# Communications.net
KiCad netlist of a schematic drawn in Altium Designer
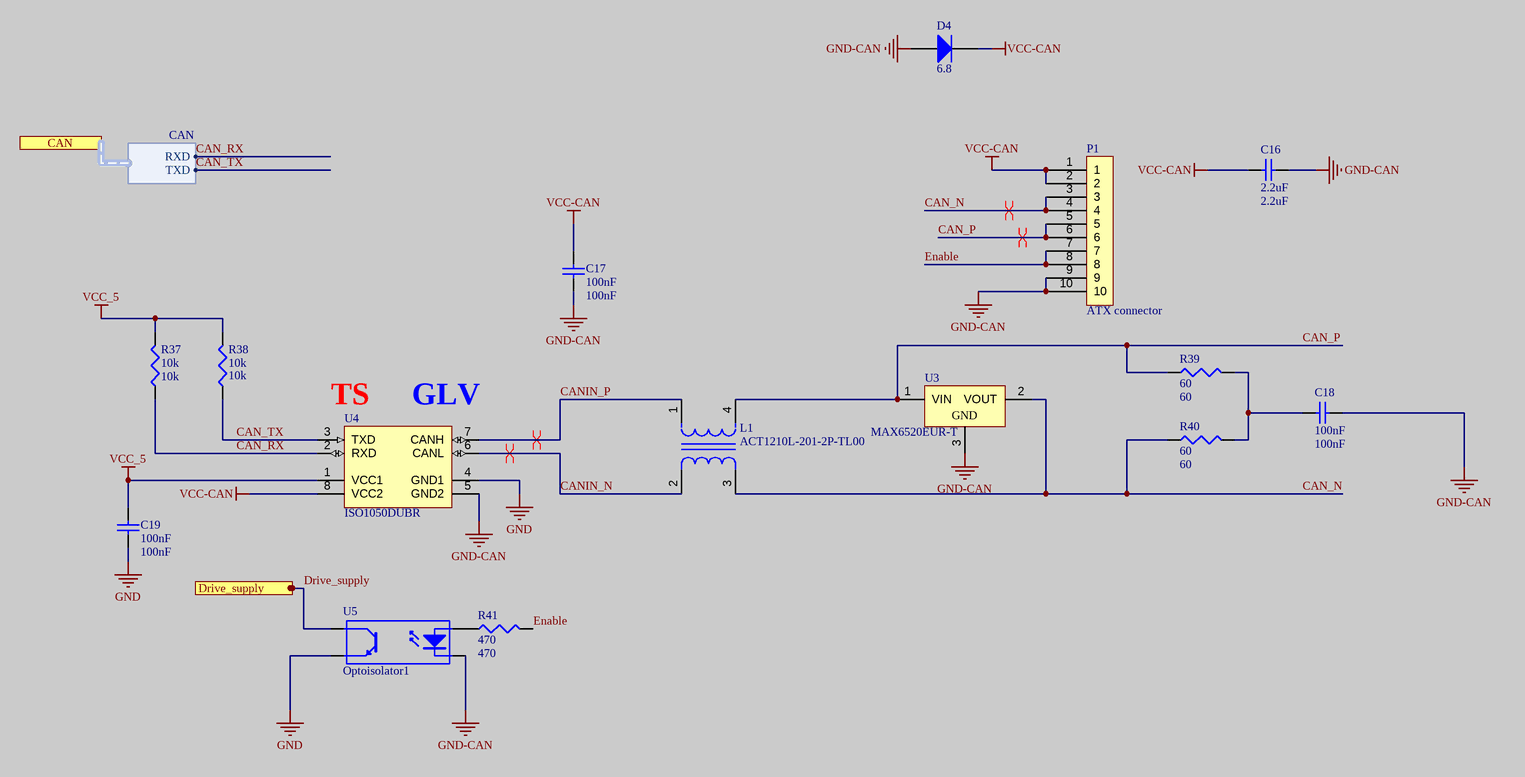
[diagram p0: Communications.SchDoc]

(export (version "E")
  (design (tool "Eeschema 10.0.6"))
  (components
    (comp (ref "C16")
      (value "2.2uF")
      (footprint "C0805")
      (description "Capacitor")
      (fields (field (name "ALTIUM_VALUE") "2.2uF") (field (name "PUBLISHER") "Altium Limited"))
      (libsource (lib "MyLibrary") (part "Capacitor"))
    )
    (comp (ref "C17")
      (value "100nF")
      (footprint "C0805")
      (description "Capacitor")
      (fields (field (name "ALTIUM_VALUE") "100nF") (field (name "PUBLISHER") "Altium Limited"))
      (libsource (lib "MyLibrary") (part "Capacitor"))
    )
    (comp (ref "C18")
      (value "100nF")
      (footprint "C0805")
      (description "Capacitor")
      (fields (field (name "ALTIUM_VALUE") "100nF") (field (name "PUBLISHER") "Altium Limited"))
      (libsource (lib "MyLibrary") (part "Capacitor"))
    )
    (comp (ref "C19")
      (value "100nF")
      (footprint "C0805")
      (description "Capacitor")
      (fields (field (name "ALTIUM_VALUE") "100nF") (field (name "PUBLISHER") "Altium Limited"))
      (libsource (lib "MyLibrary") (part "Capacitor"))
    )
    (comp (ref "D4")
      (value "6.8")
      (footprint "DIOD-SOD123-2_V")
      (description "Fast Switching Diode, 100 V, 0.15 A, -65 to 150 degC, 2-Pin?SOD123, RoHS, Tape and Reel")
      (fields (field (name "MANUFACTURER") "DiodesIncorporated"))
      (libsource (lib "1N4148W") (part "CMP-2000-04932-2"))
    )
    (comp (ref "L1")
      (value "ACT1210L-201-2P-TL00")
      (footprint "FP-ACT1210L-MFG")
      (description "CMC 200UH 70MA 2LN SMD")
      (fields
        (field (name "MANUFACTURER") "TDK")
        (field (name "OCTOPART") "https://octopart.com/act1210l-201-2p-tl00-tdk-81014617")
      )
      (libsource (lib "ACT1210L-201-2P-TL00") (part "CMP-08256-000003-1"))
    )
    (comp (ref "P1")
      (value "ATX connector")
      (footprint "ATX 10pin")
      (libsource (lib "MyLibrary") (part "ATX connector"))
    )
    (comp (ref "R37")
      (value "10k")
      (footprint "R0805")
      (description "Resistor")
      (fields (field (name "ALTIUM_VALUE") "10k") (field (name "PUBLISHER") "Altium Limited"))
      (libsource (lib "MyLibrary") (part "Resistor"))
    )
    (comp (ref "R38")
      (value "10k")
      (footprint "R0805")
      (description "Resistor")
      (fields (field (name "ALTIUM_VALUE") "10k") (field (name "PUBLISHER") "Altium Limited"))
      (libsource (lib "MyLibrary") (part "Resistor"))
    )
    (comp (ref "R39")
      (value "60")
      (footprint "R0805")
      (description "Resistor")
      (fields (field (name "ALTIUM_VALUE") "60") (field (name "PUBLISHER") "Altium Limited"))
      (libsource (lib "MyLibrary") (part "Resistor"))
    )
    (comp (ref "R40")
      (value "60")
      (footprint "R0805")
      (description "Resistor")
      (fields (field (name "ALTIUM_VALUE") "60") (field (name "PUBLISHER") "Altium Limited"))
      (libsource (lib "MyLibrary") (part "Resistor"))
    )
    (comp (ref "R41")
      (value "470")
      (footprint "R0805")
      (description "Resistor")
      (fields (field (name "ALTIUM_VALUE") "470") (field (name "PUBLISHER") "Altium Limited"))
      (libsource (lib "MyLibrary") (part "Resistor"))
    )
    (comp (ref "U3")
      (value "MAX6520EUR-T")
      (footprint "SOT23-3_N")
      (description "3-Terminal, 1.2V Voltage Reference")
      (fields (field (name "PUBLISHER") "Altium Limited"))
      (libsource (lib "Maxim Power Mgt Voltage Reference") (part "MAX6520EUR-T"))
    )
    (comp (ref "U4")
      (value "ISO1050DUBR")
      (footprint "DUB0008A_M")
      (description "Isolated CAN Transceiver, -55 to 105 degC, 8-pin SOP (DUB), Green (RoHS & no Sb/Br)")
      (fields (field (name "MANUFACTURER") "Texas Instruments"))
      (libsource (lib "Components - 05.09.22 - 15.55") (part "CMP-0315-00093-2"))
    )
    (comp (ref "U5")
      (value "Optoisolator1")
      (footprint "DIP-4")
      (description "4-Pin Phototransistor Optocoupler")
      (fields (field (name "PUBLISHER") "Altium Limited"))
      (libsource (lib "Miscellaneous Devices") (part "Optoisolator1"))
    )
  )
  (nets
    (net (code "2") (name "/CANIN_N") (class "Default")
      (node (ref "L1") (pin "2") (pinfunction "2_2") (pintype "passive"))
      (node (ref "U4") (pin "6") (pinfunction "CANL_6") (pintype "bidirectional"))
    )
    (net (code "3") (name "/CANIN_P") (class "Default")
      (node (ref "L1") (pin "1") (pinfunction "1_1") (pintype "passive"))
      (node (ref "U4") (pin "7") (pinfunction "CANH_7") (pintype "bidirectional"))
    )
    (net (code "4") (name "/CAN_N") (class "Default")
      (node (ref "L1") (pin "3") (pinfunction "3_3") (pintype "passive"))
      (node (ref "P1") (pin "3") (pinfunction "3_3") (pintype "passive"))
      (node (ref "P1") (pin "4") (pinfunction "4_4") (pintype "passive"))
      (node (ref "R40") (pin "1") (pinfunction "1_1") (pintype "passive"))
      (node (ref "U3") (pin "2") (pinfunction "VOUT_2") (pintype "passive"))
    )
    (net (code "5") (name "/CAN_P") (class "Default")
      (node (ref "L1") (pin "4") (pinfunction "4_4") (pintype "passive"))
      (node (ref "P1") (pin "5") (pinfunction "5_5") (pintype "passive"))
      (node (ref "P1") (pin "6") (pinfunction "6_6") (pintype "passive"))
      (node (ref "R39") (pin "1") (pinfunction "1_1") (pintype "passive"))
      (node (ref "U3") (pin "1") (pinfunction "VIN_1") (pintype "passive"))
    )
    (net (code "6") (name "/CAN_RX") (class "Default")
      (node (ref "R37") (pin "1") (pinfunction "1_1") (pintype "passive"))
      (node (ref "U4") (pin "2") (pinfunction "RXD_2") (pintype "bidirectional"))
    )
    (net (code "7") (name "/CAN_TX") (class "Default")
      (node (ref "R38") (pin "1") (pinfunction "1_1") (pintype "passive"))
      (node (ref "U4") (pin "3") (pinfunction "TXD_3") (pintype "input"))
    )
    (net (code "8") (name "/Drive_supply") (class "Default")
      (node (ref "U5") (pin "4") (pinfunction "C_4") (pintype "passive"))
    )
    (net (code "9") (name "/Enable") (class "Default")
      (node (ref "P1") (pin "7") (pinfunction "7_7") (pintype "passive"))
      (node (ref "P1") (pin "8") (pinfunction "8_8") (pintype "passive"))
      (node (ref "R41") (pin "2") (pinfunction "2_2") (pintype "passive"))
    )
    (net (code "11") (name "GND") (class "Default")
      (node (ref "C19") (pin "2") (pinfunction "2_2") (pintype "passive"))
      (node (ref "U4") (pin "4") (pinfunction "GND1_4") (pintype "power_in"))
      (node (ref "U5") (pin "3") (pinfunction "E_3") (pintype "passive"))
    )
    (net (code "12") (name "GND-CAN") (class "Default")
      (node (ref "C16") (pin "2") (pinfunction "2_2") (pintype "passive"))
      (node (ref "C17") (pin "1") (pinfunction "1_1") (pintype "passive"))
      (node (ref "C18") (pin "1") (pinfunction "1_1") (pintype "passive"))
      (node (ref "D4") (pin "1") (pinfunction "A_1") (pintype "passive"))
      (node (ref "P1") (pin "10") (pinfunction "10_10") (pintype "passive"))
      (node (ref "P1") (pin "9") (pinfunction "9_9") (pintype "passive"))
      (node (ref "U3") (pin "3") (pinfunction "GND_3") (pintype "power_in"))
      (node (ref "U4") (pin "5") (pinfunction "GND2_5") (pintype "power_in"))
      (node (ref "U5") (pin "2") (pinfunction "K_2") (pintype "passive"))
    )
    (net (code "13") (name "Net-(C18-Pad2)") (class "Default")
      (node (ref "C18") (pin "2") (pinfunction "2_2") (pintype "passive"))
      (node (ref "R39") (pin "2") (pinfunction "2_2") (pintype "passive"))
      (node (ref "R40") (pin "2") (pinfunction "2_2") (pintype "passive"))
    )
    (net (code "14") (name "Net-(U5-A)") (class "Default")
      (node (ref "R41") (pin "1") (pinfunction "1_1") (pintype "passive"))
      (node (ref "U5") (pin "1") (pinfunction "A_1") (pintype "passive"))
    )
    (net (code "15") (name "VCC-CAN") (class "Default")
      (node (ref "C16") (pin "1") (pinfunction "1_1") (pintype "passive"))
      (node (ref "C17") (pin "2") (pinfunction "2_2") (pintype "passive"))
      (node (ref "D4") (pin "2") (pinfunction "K_2") (pintype "passive"))
      (node (ref "P1") (pin "1") (pinfunction "1_1") (pintype "passive"))
      (node (ref "P1") (pin "2") (pinfunction "2_2") (pintype "passive"))
      (node (ref "U4") (pin "8") (pinfunction "VCC2_8") (pintype "power_in"))
    )
    (net (code "16") (name "VCC_5") (class "Default")
      (node (ref "C19") (pin "1") (pinfunction "1_1") (pintype "passive"))
      (node (ref "R37") (pin "2") (pinfunction "2_2") (pintype "passive"))
      (node (ref "R38") (pin "2") (pinfunction "2_2") (pintype "passive"))
      (node (ref "U4") (pin "1") (pinfunction "VCC1_1") (pintype "power_in"))
    )
  )
)
